# fpga-prom.net
KiCad netlist of a schematic drawn in Altium Designer
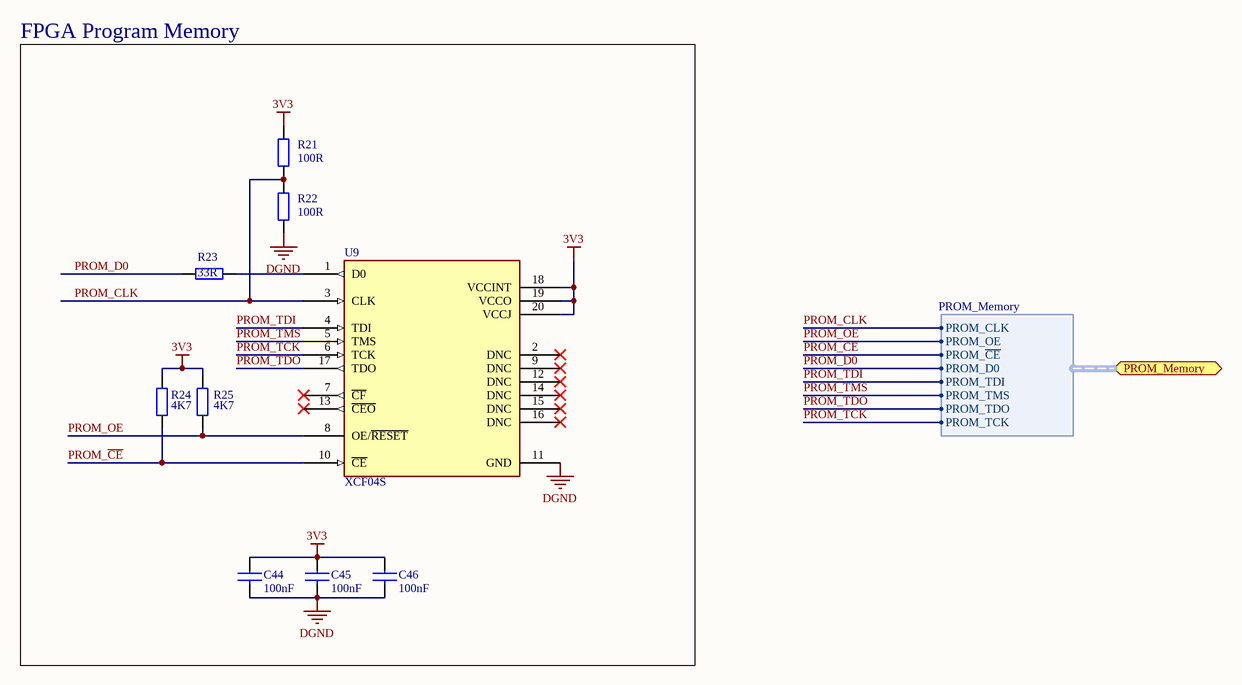
[diagram p0: fpga-prom.SchDoc]

(export (version "E")
  (design (tool "Eeschema 10.0.6"))
  (components
    (comp (ref "C44")
      (value "100nF")
      (footprint "SM/C_0603")
      (description "Ceramic multi-layer")
      (fields (field (name "MANUFACTURER") "AVX") (field (name "VOLTAGE") "16V"))
      (libsource (lib "Database_heig-vd") (part "Cap"))
    )
    (comp (ref "C45")
      (value "100nF")
      (footprint "SM/C_0603")
      (description "Ceramic multi-layer")
      (fields (field (name "MANUFACTURER") "AVX") (field (name "VOLTAGE") "16V"))
      (libsource (lib "Database_heig-vd") (part "Cap"))
    )
    (comp (ref "C46")
      (value "100nF")
      (footprint "SM/C_0603")
      (description "Ceramic multi-layer")
      (fields (field (name "MANUFACTURER") "AVX") (field (name "VOLTAGE") "16V"))
      (libsource (lib "Database_heig-vd") (part "Cap"))
    )
    (comp (ref "R21")
      (value "100R")
      (footprint "SM/R_0603")
      (description "Résistance 0603 63mW 1% 100R")
      (fields (field (name "MANUFACTURER") "Multicomp") (field (name "POWER") "63mW"))
      (libsource (lib "Database_heig-vd") (part "Res"))
    )
    (comp (ref "R22")
      (value "100R")
      (footprint "SM/R_0603")
      (description "Résistance 0603 63mW 1% 100R")
      (fields (field (name "MANUFACTURER") "Multicomp") (field (name "POWER") "63mW"))
      (libsource (lib "Database_heig-vd") (part "Res"))
    )
    (comp (ref "R23")
      (value "33R")
      (footprint "SM/R_0603")
      (description "Résistance 0603 63mW 1% 33R")
      (fields (field (name "MANUFACTURER") "Multicomp") (field (name "POWER") "63mW"))
      (libsource (lib "Database_heig-vd") (part "Res"))
    )
    (comp (ref "R24")
      (value "4K7")
      (footprint "SM/R_0603")
      (description "Résistance 0603 63mW 1% 4K7")
      (fields (field (name "MANUFACTURER") "Multicomp") (field (name "POWER") "63mW"))
      (libsource (lib "Database_heig-vd") (part "Res"))
    )
    (comp (ref "R25")
      (value "4K7")
      (footprint "SM/R_0603")
      (description "Résistance 0603 63mW 1% 4K7")
      (fields (field (name "MANUFACTURER") "Multicomp") (field (name "POWER") "63mW"))
      (libsource (lib "Database_heig-vd") (part "Res"))
    )
    (comp (ref "U9")
      (value "XCF04S")
      (footprint "TSSOP-20")
      (description "Platform Flash In-System Programmable Configuration PROMs")
      (fields (field (name "MANUFACTURER") "Xilinx"))
      (libsource (lib "MAQTRAIN") (part "XCF04S"))
    )
  )
  (nets
    (net (code "2") (name "/PROM_CLK") (class "Default")
      (node (ref "R21") (pin "2") (pinfunction "2_2") (pintype "passive"))
      (node (ref "R22") (pin "1") (pinfunction "1_1") (pintype "passive"))
      (node (ref "U9") (pin "3") (pinfunction "CLK_3") (pintype "input"))
    )
    (net (code "3") (name "/PROM_D0") (class "Default")
      (node (ref "R23") (pin "1") (pinfunction "1_1") (pintype "passive"))
    )
    (net (code "4") (name "/PROM_OE") (class "Default")
      (node (ref "R25") (pin "2") (pinfunction "2_2") (pintype "passive"))
      (node (ref "U9") (pin "8") (pinfunction "OE/~{RESET}_8") (pintype "open_collector"))
    )
    (net (code "5") (name "/PROM_TCK") (class "Default")
      (node (ref "U9") (pin "6") (pinfunction "TCK_6") (pintype "input"))
    )
    (net (code "6") (name "/PROM_TDI") (class "Default")
      (node (ref "U9") (pin "4") (pinfunction "TDI_4") (pintype "input"))
    )
    (net (code "7") (name "/PROM_TDO") (class "Default")
      (node (ref "U9") (pin "17") (pinfunction "TDO_17") (pintype "output"))
    )
    (net (code "8") (name "/PROM_TMS") (class "Default")
      (node (ref "U9") (pin "5") (pinfunction "TMS_5") (pintype "input"))
    )
    (net (code "9") (name "/PROM_~{CE}") (class "Default")
      (node (ref "R24") (pin "2") (pinfunction "2_2") (pintype "passive"))
      (node (ref "U9") (pin "10") (pinfunction "~{CE}_10") (pintype "input"))
    )
    (net (code "11") (name "3V3") (class "Default")
      (node (ref "C44") (pin "1") (pinfunction "1_1") (pintype "passive"))
      (node (ref "C45") (pin "1") (pinfunction "1_1") (pintype "passive"))
      (node (ref "C46") (pin "1") (pinfunction "1_1") (pintype "passive"))
      (node (ref "R21") (pin "1") (pinfunction "1_1") (pintype "passive"))
      (node (ref "R24") (pin "1") (pinfunction "1_1") (pintype "passive"))
      (node (ref "R25") (pin "1") (pinfunction "1_1") (pintype "passive"))
      (node (ref "U9") (pin "18") (pinfunction "VCCINT_18") (pintype "power_in"))
      (node (ref "U9") (pin "19") (pinfunction "VCCO_19") (pintype "power_in"))
      (node (ref "U9") (pin "20") (pinfunction "VCCJ_20") (pintype "power_in"))
    )
    (net (code "12") (name "DGND") (class "Default")
      (node (ref "C44") (pin "2") (pinfunction "2_2") (pintype "passive"))
      (node (ref "C45") (pin "2") (pinfunction "2_2") (pintype "passive"))
      (node (ref "C46") (pin "2") (pinfunction "2_2") (pintype "passive"))
      (node (ref "R22") (pin "2") (pinfunction "2_2") (pintype "passive"))
      (node (ref "U9") (pin "11") (pinfunction "GND_11") (pintype "power_in"))
    )
    (net (code "13") (name "Net-(U9-D0)") (class "Default")
      (node (ref "R23") (pin "2") (pinfunction "2_2") (pintype "passive"))
      (node (ref "U9") (pin "1") (pinfunction "D0_1") (pintype "output"))
    )
    (net (code "14") (name "unconnected-(U9-CEO-Pad13)") (class "Default")
      (node (ref "U9") (pin "13") (pinfunction "CEO_13") (pintype "output+no_connect"))
    )
    (net (code "15") (name "unconnected-(U9-CF-Pad7)") (class "Default")
      (node (ref "U9") (pin "7") (pinfunction "CF_7") (pintype "output+no_connect"))
    )
    (net (code "16") (name "unconnected-(U9-DNC-Pad2)") (class "Default")
      (node (ref "U9") (pin "2") (pinfunction "DNC_2") (pintype "passive+no_connect"))
    )
    (net (code "17") (name "unconnected-(U9-DNC-Pad9)") (class "Default")
      (node (ref "U9") (pin "9") (pinfunction "DNC_9") (pintype "passive+no_connect"))
    )
    (net (code "18") (name "unconnected-(U9-DNC-Pad12)") (class "Default")
      (node (ref "U9") (pin "12") (pinfunction "DNC_12") (pintype "passive+no_connect"))
    )
    (net (code "19") (name "unconnected-(U9-DNC-Pad14)") (class "Default")
      (node (ref "U9") (pin "14") (pinfunction "DNC_14") (pintype "passive+no_connect"))
    )
    (net (code "20") (name "unconnected-(U9-DNC-Pad15)") (class "Default")
      (node (ref "U9") (pin "15") (pinfunction "DNC_15") (pintype "passive+no_connect"))
    )
    (net (code "21") (name "unconnected-(U9-DNC-Pad16)") (class "Default")
      (node (ref "U9") (pin "16") (pinfunction "DNC_16") (pintype "passive+no_connect"))
    )
  )
)
